# BleDemoBoard.net
KiCad netlist of a schematic drawn in Altium Designer
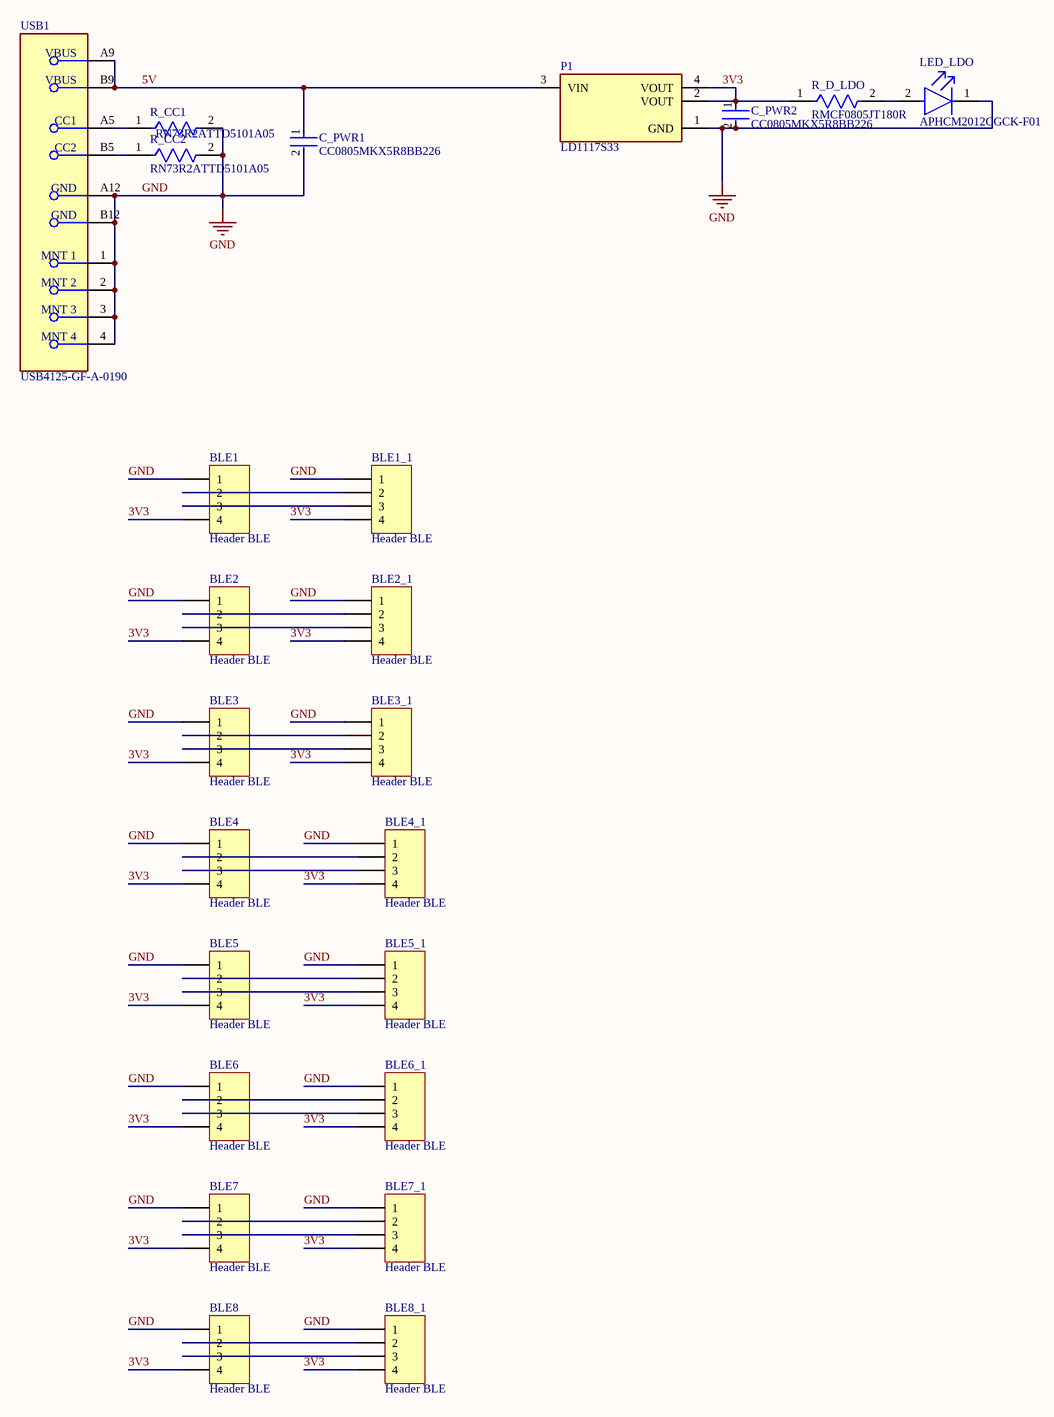
[diagram p0: BleDemoBoard.SchDoc]

(export (version "E")
  (design (tool "Eeschema 10.0.6"))
  (components
    (comp (ref "BLE1")
      (value "Header BLE")
      (footprint "HDR1X4")
      (description "Header, 4-Pin")
      (fields (field (name "PUBLISHER") "Altium Limited"))
      (libsource (lib "Miscellaneous Connectors") (part "Header 4"))
    )
    (comp (ref "BLE1_1")
      (value "Header BLE")
      (footprint "HDR1X4")
      (description "Header, 4-Pin")
      (fields (field (name "PUBLISHER") "Altium Limited"))
      (libsource (lib "Miscellaneous Connectors") (part "Header 4"))
    )
    (comp (ref "BLE2")
      (value "Header BLE")
      (footprint "HDR1X4")
      (description "Header, 4-Pin")
      (fields (field (name "PUBLISHER") "Altium Limited"))
      (libsource (lib "Miscellaneous Connectors") (part "Header 4"))
    )
    (comp (ref "BLE2_1")
      (value "Header BLE")
      (footprint "HDR1X4")
      (description "Header, 4-Pin")
      (fields (field (name "PUBLISHER") "Altium Limited"))
      (libsource (lib "Miscellaneous Connectors") (part "Header 4"))
    )
    (comp (ref "BLE3")
      (value "Header BLE")
      (footprint "HDR1X4")
      (description "Header, 4-Pin")
      (fields (field (name "PUBLISHER") "Altium Limited"))
      (libsource (lib "Miscellaneous Connectors") (part "Header 4"))
    )
    (comp (ref "BLE3_1")
      (value "Header BLE")
      (footprint "HDR1X4")
      (description "Header, 4-Pin")
      (fields (field (name "PUBLISHER") "Altium Limited"))
      (libsource (lib "Miscellaneous Connectors") (part "Header 4"))
    )
    (comp (ref "BLE4")
      (value "Header BLE")
      (footprint "HDR1X4")
      (description "Header, 4-Pin")
      (fields (field (name "PUBLISHER") "Altium Limited"))
      (libsource (lib "Miscellaneous Connectors") (part "Header 4"))
    )
    (comp (ref "BLE4_1")
      (value "Header BLE")
      (footprint "HDR1X4")
      (description "Header, 4-Pin")
      (fields (field (name "PUBLISHER") "Altium Limited"))
      (libsource (lib "Miscellaneous Connectors") (part "Header 4"))
    )
    (comp (ref "BLE5")
      (value "Header BLE")
      (footprint "HDR1X4")
      (description "Header, 4-Pin")
      (fields (field (name "PUBLISHER") "Altium Limited"))
      (libsource (lib "Miscellaneous Connectors") (part "Header 4"))
    )
    (comp (ref "BLE5_1")
      (value "Header BLE")
      (footprint "HDR1X4")
      (description "Header, 4-Pin")
      (fields (field (name "PUBLISHER") "Altium Limited"))
      (libsource (lib "Miscellaneous Connectors") (part "Header 4"))
    )
    (comp (ref "BLE6")
      (value "Header BLE")
      (footprint "HDR1X4")
      (description "Header, 4-Pin")
      (fields (field (name "PUBLISHER") "Altium Limited"))
      (libsource (lib "Miscellaneous Connectors") (part "Header 4"))
    )
    (comp (ref "BLE6_1")
      (value "Header BLE")
      (footprint "HDR1X4")
      (description "Header, 4-Pin")
      (fields (field (name "PUBLISHER") "Altium Limited"))
      (libsource (lib "Miscellaneous Connectors") (part "Header 4"))
    )
    (comp (ref "BLE7")
      (value "Header BLE")
      (footprint "HDR1X4")
      (description "Header, 4-Pin")
      (fields (field (name "PUBLISHER") "Altium Limited"))
      (libsource (lib "Miscellaneous Connectors") (part "Header 4"))
    )
    (comp (ref "BLE7_1")
      (value "Header BLE")
      (footprint "HDR1X4")
      (description "Header, 4-Pin")
      (fields (field (name "PUBLISHER") "Altium Limited"))
      (libsource (lib "Miscellaneous Connectors") (part "Header 4"))
    )
    (comp (ref "BLE8")
      (value "Header BLE")
      (footprint "HDR1X4")
      (description "Header, 4-Pin")
      (fields (field (name "PUBLISHER") "Altium Limited"))
      (libsource (lib "Miscellaneous Connectors") (part "Header 4"))
    )
    (comp (ref "BLE8_1")
      (value "Header BLE")
      (footprint "HDR1X4")
      (description "Header, 4-Pin")
      (fields (field (name "PUBLISHER") "Altium Limited"))
      (libsource (lib "Miscellaneous Connectors") (part "Header 4"))
    )
    (comp (ref "C_PWR1")
      (value "CC0805MKX5R8BB226")
      (footprint "FP-CC0805-0_2-1_45-IPC_C")
      (description "CAP CER 22UF 25V X5R 0805")
      (fields (field (name "TOLERANCE") "20%"))
      (libsource (lib "Altium Content Vault") (part "11868f565c42a9108669ba33697ecf6"))
    )
    (comp (ref "C_PWR2")
      (value "CC0805MKX5R8BB226")
      (footprint "FP-CC0805-0_2-1_45-IPC_C")
      (description "CAP CER 22UF 25V X5R 0805")
      (fields (field (name "TOLERANCE") "20%"))
      (libsource (lib "Altium Content Vault") (part "11868f565c42a9108669ba33697ecf6"))
    )
    (comp (ref "LED_LDO")
      (value "APHCM2012CGCK-F01")
      (footprint "FP-APHCM2012CGCK-F01-MFG")
      (description "LED GREEN CLEAR CHIP SMD")
      (libsource (lib "Altium Content Vault") (part "8706943c75ba83719d021d2fdc84c58"))
    )
    (comp (ref "P1")
      (value "LD1117S33")
      (footprint "FP-SOT-223-0046067_14-MFG")
      (description "IC REG LINEAR 3.3V 800MA SOT223")
      (libsource (lib "Altium Content Vault") (part "7818869c5c16ceab15634627166a29d"))
    )
    (comp (ref "R_CC1")
      (value "RN73R2ATTD5101A05")
      (footprint "FP-RN73R2A-IPC_C")
      (description "5.1kΩ ±0.05% 0.125W, 1/8W Chip Resistor 0805 (2012 Metric) Moisture Resistant Thin Film")
      (libsource (lib "Altium Content Vault") (part "1029c3af85768c4190bb7ad29bc67b5"))
    )
    (comp (ref "R_CC2")
      (value "RN73R2ATTD5101A05")
      (footprint "FP-RN73R2A-IPC_C")
      (description "5.1kΩ ±0.05% 0.125W, 1/8W Chip Resistor 0805 (2012 Metric) Moisture Resistant Thin Film")
      (libsource (lib "Altium Content Vault") (part "1029c3af85768c4190bb7ad29bc67b5"))
    )
    (comp (ref "R_D_LDO")
      (value "RMCF0805JT180R")
      (footprint "FP-RMCF0805-IPC_B")
      (description "180Ω ±5% 0.125W 0805 Thick Film Chip Resistor AEC-Q200 compliant")
      (fields (field (name "TOLERANCE") "5%"))
      (libsource (lib "Altium Content Vault") (part "1029c3af85768c4190bb7ad29bc67b5"))
    )
    (comp (ref "USB1")
      (value "USB4125-GF-A-0190")
      (footprint "FP-USB4125-GF-A-0190-MFG")
      (description "CONN RCPT TYPE C 6P SMD RA")
      (libsource (lib "Altium Content Vault") (part "a055484d46e58b234844902c9fd883a"))
    )
  )
  (nets
    (net (code "1") (name "/3V3") (class "Default")
      (node (ref "BLE1") (pin "4") (pinfunction "4_4") (pintype "passive"))
      (node (ref "BLE1_1") (pin "4") (pinfunction "4_4") (pintype "passive"))
      (node (ref "BLE2") (pin "4") (pinfunction "4_4") (pintype "passive"))
      (node (ref "BLE2_1") (pin "4") (pinfunction "4_4") (pintype "passive"))
      (node (ref "BLE3") (pin "4") (pinfunction "4_4") (pintype "passive"))
      (node (ref "BLE3_1") (pin "4") (pinfunction "4_4") (pintype "passive"))
      (node (ref "BLE4") (pin "4") (pinfunction "4_4") (pintype "passive"))
      (node (ref "BLE4_1") (pin "4") (pinfunction "4_4") (pintype "passive"))
      (node (ref "BLE5") (pin "4") (pinfunction "4_4") (pintype "passive"))
      (node (ref "BLE5_1") (pin "4") (pinfunction "4_4") (pintype "passive"))
      (node (ref "BLE6") (pin "4") (pinfunction "4_4") (pintype "passive"))
      (node (ref "BLE6_1") (pin "4") (pinfunction "4_4") (pintype "passive"))
      (node (ref "BLE7") (pin "4") (pinfunction "4_4") (pintype "passive"))
      (node (ref "BLE7_1") (pin "4") (pinfunction "4_4") (pintype "passive"))
      (node (ref "BLE8") (pin "4") (pinfunction "4_4") (pintype "passive"))
      (node (ref "BLE8_1") (pin "4") (pinfunction "4_4") (pintype "passive"))
      (node (ref "C_PWR2") (pin "1") (pinfunction "1_1") (pintype "passive"))
      (node (ref "P1") (pin "2") (pinfunction "VOUT_2") (pintype "power_in"))
      (node (ref "P1") (pin "4") (pinfunction "VOUT_4") (pintype "power_in"))
      (node (ref "R_D_LDO") (pin "1") (pinfunction "1_1") (pintype "passive"))
    )
    (net (code "2") (name "/5V") (class "Default")
      (node (ref "C_PWR1") (pin "1") (pinfunction "1_1") (pintype "passive"))
      (node (ref "P1") (pin "3") (pinfunction "VIN_3") (pintype "power_in"))
      (node (ref "USB1") (pin "A9") (pinfunction "VBUS_A9") (pintype "passive"))
      (node (ref "USB1") (pin "B9") (pinfunction "VBUS_B9") (pintype "passive"))
    )
    (net (code "3") (name "GND") (class "Default")
      (node (ref "BLE1") (pin "1") (pinfunction "1_1") (pintype "passive"))
      (node (ref "BLE1_1") (pin "1") (pinfunction "1_1") (pintype "passive"))
      (node (ref "BLE2") (pin "1") (pinfunction "1_1") (pintype "passive"))
      (node (ref "BLE2_1") (pin "1") (pinfunction "1_1") (pintype "passive"))
      (node (ref "BLE3") (pin "1") (pinfunction "1_1") (pintype "passive"))
      (node (ref "BLE3_1") (pin "1") (pinfunction "1_1") (pintype "passive"))
      (node (ref "BLE4") (pin "1") (pinfunction "1_1") (pintype "passive"))
      (node (ref "BLE4_1") (pin "1") (pinfunction "1_1") (pintype "passive"))
      (node (ref "BLE5") (pin "1") (pinfunction "1_1") (pintype "passive"))
      (node (ref "BLE5_1") (pin "1") (pinfunction "1_1") (pintype "passive"))
      (node (ref "BLE6") (pin "1") (pinfunction "1_1") (pintype "passive"))
      (node (ref "BLE6_1") (pin "1") (pinfunction "1_1") (pintype "passive"))
      (node (ref "BLE7") (pin "1") (pinfunction "1_1") (pintype "passive"))
      (node (ref "BLE7_1") (pin "1") (pinfunction "1_1") (pintype "passive"))
      (node (ref "BLE8") (pin "1") (pinfunction "1_1") (pintype "passive"))
      (node (ref "BLE8_1") (pin "1") (pinfunction "1_1") (pintype "passive"))
      (node (ref "C_PWR1") (pin "2") (pinfunction "2_2") (pintype "passive"))
      (node (ref "C_PWR2") (pin "2") (pinfunction "2_2") (pintype "passive"))
      (node (ref "LED_LDO") (pin "1") (pinfunction "C_1") (pintype "passive"))
      (node (ref "P1") (pin "1") (pinfunction "GND_1") (pintype "power_in"))
      (node (ref "R_CC1") (pin "2") (pinfunction "2_2") (pintype "passive"))
      (node (ref "R_CC2") (pin "2") (pinfunction "2_2") (pintype "passive"))
      (node (ref "USB1") (pin "1") (pinfunction "MNT_1_1") (pintype "passive"))
      (node (ref "USB1") (pin "2") (pinfunction "MNT_2_2") (pintype "passive"))
      (node (ref "USB1") (pin "3") (pinfunction "MNT_3_3") (pintype "passive"))
      (node (ref "USB1") (pin "4") (pinfunction "MNT_4_4") (pintype "passive"))
      (node (ref "USB1") (pin "A12") (pinfunction "GND_A12") (pintype "passive"))
      (node (ref "USB1") (pin "B12") (pinfunction "GND_B12") (pintype "passive"))
    )
    (net (code "4") (name "Net-(BLE1-Pad2)") (class "Default")
      (node (ref "BLE1") (pin "2") (pinfunction "2_2") (pintype "passive"))
      (node (ref "BLE1_1") (pin "2") (pinfunction "2_2") (pintype "passive"))
    )
    (net (code "5") (name "Net-(BLE1-Pad3)") (class "Default")
      (node (ref "BLE1") (pin "3") (pinfunction "3_3") (pintype "passive"))
      (node (ref "BLE1_1") (pin "3") (pinfunction "3_3") (pintype "passive"))
    )
    (net (code "6") (name "Net-(BLE2-Pad2)") (class "Default")
      (node (ref "BLE2") (pin "2") (pinfunction "2_2") (pintype "passive"))
      (node (ref "BLE2_1") (pin "2") (pinfunction "2_2") (pintype "passive"))
    )
    (net (code "7") (name "Net-(BLE2-Pad3)") (class "Default")
      (node (ref "BLE2") (pin "3") (pinfunction "3_3") (pintype "passive"))
      (node (ref "BLE2_1") (pin "3") (pinfunction "3_3") (pintype "passive"))
    )
    (net (code "8") (name "Net-(BLE3-Pad2)") (class "Default")
      (node (ref "BLE3") (pin "2") (pinfunction "2_2") (pintype "passive"))
      (node (ref "BLE3_1") (pin "2") (pinfunction "2_2") (pintype "passive"))
    )
    (net (code "9") (name "Net-(BLE3-Pad3)") (class "Default")
      (node (ref "BLE3") (pin "3") (pinfunction "3_3") (pintype "passive"))
      (node (ref "BLE3_1") (pin "3") (pinfunction "3_3") (pintype "passive"))
    )
    (net (code "10") (name "Net-(BLE4-Pad2)") (class "Default")
      (node (ref "BLE4") (pin "2") (pinfunction "2_2") (pintype "passive"))
      (node (ref "BLE4_1") (pin "2") (pinfunction "2_2") (pintype "passive"))
    )
    (net (code "11") (name "Net-(BLE4-Pad3)") (class "Default")
      (node (ref "BLE4") (pin "3") (pinfunction "3_3") (pintype "passive"))
      (node (ref "BLE4_1") (pin "3") (pinfunction "3_3") (pintype "passive"))
    )
    (net (code "12") (name "Net-(BLE5-Pad2)") (class "Default")
      (node (ref "BLE5") (pin "2") (pinfunction "2_2") (pintype "passive"))
      (node (ref "BLE5_1") (pin "2") (pinfunction "2_2") (pintype "passive"))
    )
    (net (code "13") (name "Net-(BLE5-Pad3)") (class "Default")
      (node (ref "BLE5") (pin "3") (pinfunction "3_3") (pintype "passive"))
      (node (ref "BLE5_1") (pin "3") (pinfunction "3_3") (pintype "passive"))
    )
    (net (code "14") (name "Net-(BLE6-Pad2)") (class "Default")
      (node (ref "BLE6") (pin "2") (pinfunction "2_2") (pintype "passive"))
      (node (ref "BLE6_1") (pin "2") (pinfunction "2_2") (pintype "passive"))
    )
    (net (code "15") (name "Net-(BLE6-Pad3)") (class "Default")
      (node (ref "BLE6") (pin "3") (pinfunction "3_3") (pintype "passive"))
      (node (ref "BLE6_1") (pin "3") (pinfunction "3_3") (pintype "passive"))
    )
    (net (code "16") (name "Net-(BLE7-Pad2)") (class "Default")
      (node (ref "BLE7") (pin "2") (pinfunction "2_2") (pintype "passive"))
      (node (ref "BLE7_1") (pin "2") (pinfunction "2_2") (pintype "passive"))
    )
    (net (code "17") (name "Net-(BLE7-Pad3)") (class "Default")
      (node (ref "BLE7") (pin "3") (pinfunction "3_3") (pintype "passive"))
      (node (ref "BLE7_1") (pin "3") (pinfunction "3_3") (pintype "passive"))
    )
    (net (code "18") (name "Net-(BLE8-Pad2)") (class "Default")
      (node (ref "BLE8") (pin "2") (pinfunction "2_2") (pintype "passive"))
      (node (ref "BLE8_1") (pin "2") (pinfunction "2_2") (pintype "passive"))
    )
    (net (code "19") (name "Net-(BLE8-Pad3)") (class "Default")
      (node (ref "BLE8") (pin "3") (pinfunction "3_3") (pintype "passive"))
      (node (ref "BLE8_1") (pin "3") (pinfunction "3_3") (pintype "passive"))
    )
    (net (code "20") (name "Net-(LED_LDO-A)") (class "Default")
      (node (ref "LED_LDO") (pin "2") (pinfunction "A_2") (pintype "passive"))
      (node (ref "R_D_LDO") (pin "2") (pinfunction "2_2") (pintype "passive"))
    )
    (net (code "21") (name "Net-(USB1-CC1)") (class "Default")
      (node (ref "R_CC1") (pin "1") (pinfunction "1_1") (pintype "passive"))
      (node (ref "USB1") (pin "A5") (pinfunction "CC1_A5") (pintype "passive"))
    )
    (net (code "22") (name "Net-(USB1-CC2)") (class "Default")
      (node (ref "R_CC2") (pin "1") (pinfunction "1_1") (pintype "passive"))
      (node (ref "USB1") (pin "B5") (pinfunction "CC2_B5") (pintype "passive"))
    )
  )
)
